# Ideamart_NB-IoT_Dev_Board.net
KiCad netlist of a schematic drawn in EAGLE
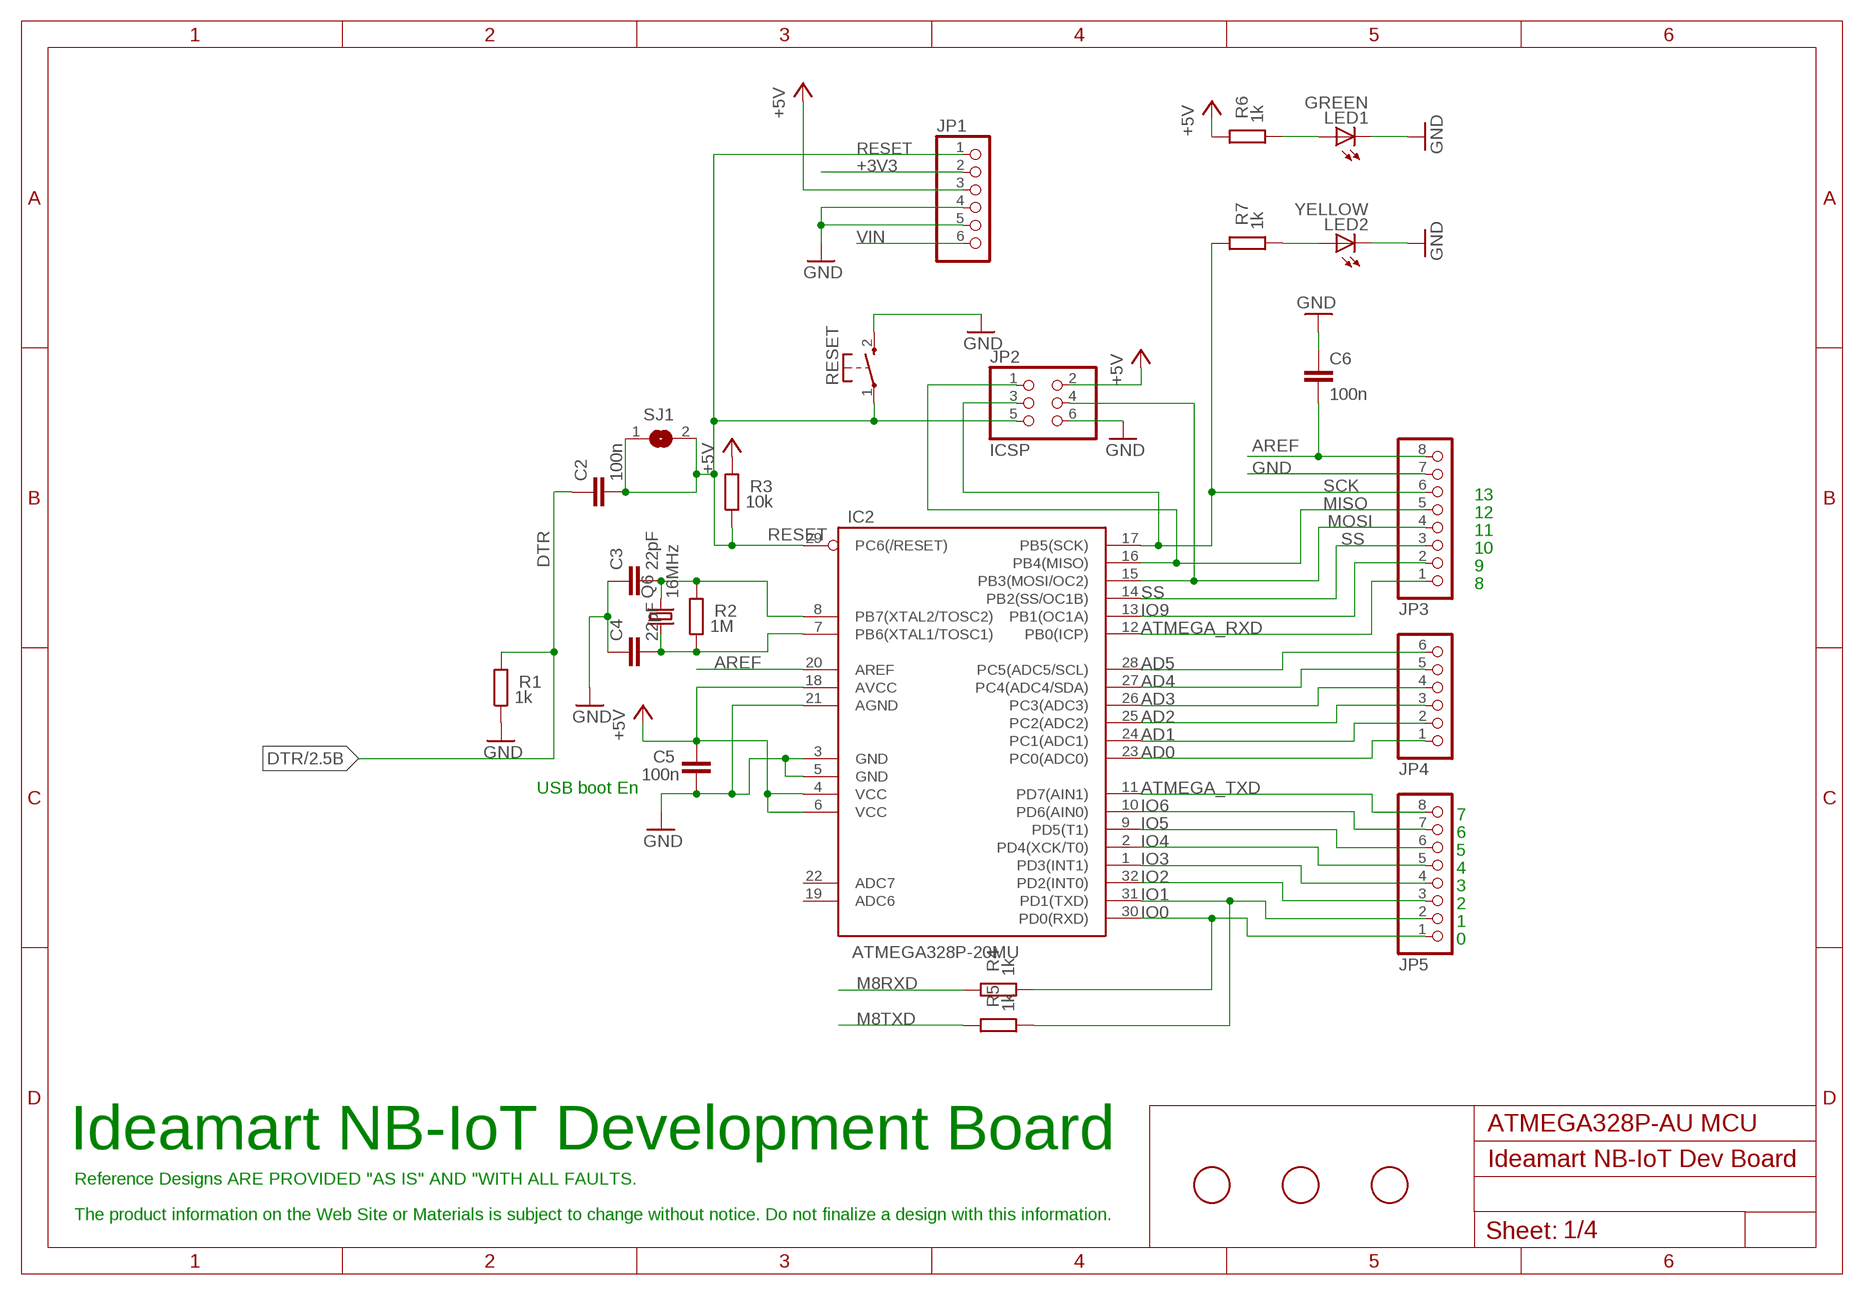
[diagram p0: schematic, sheet 1]
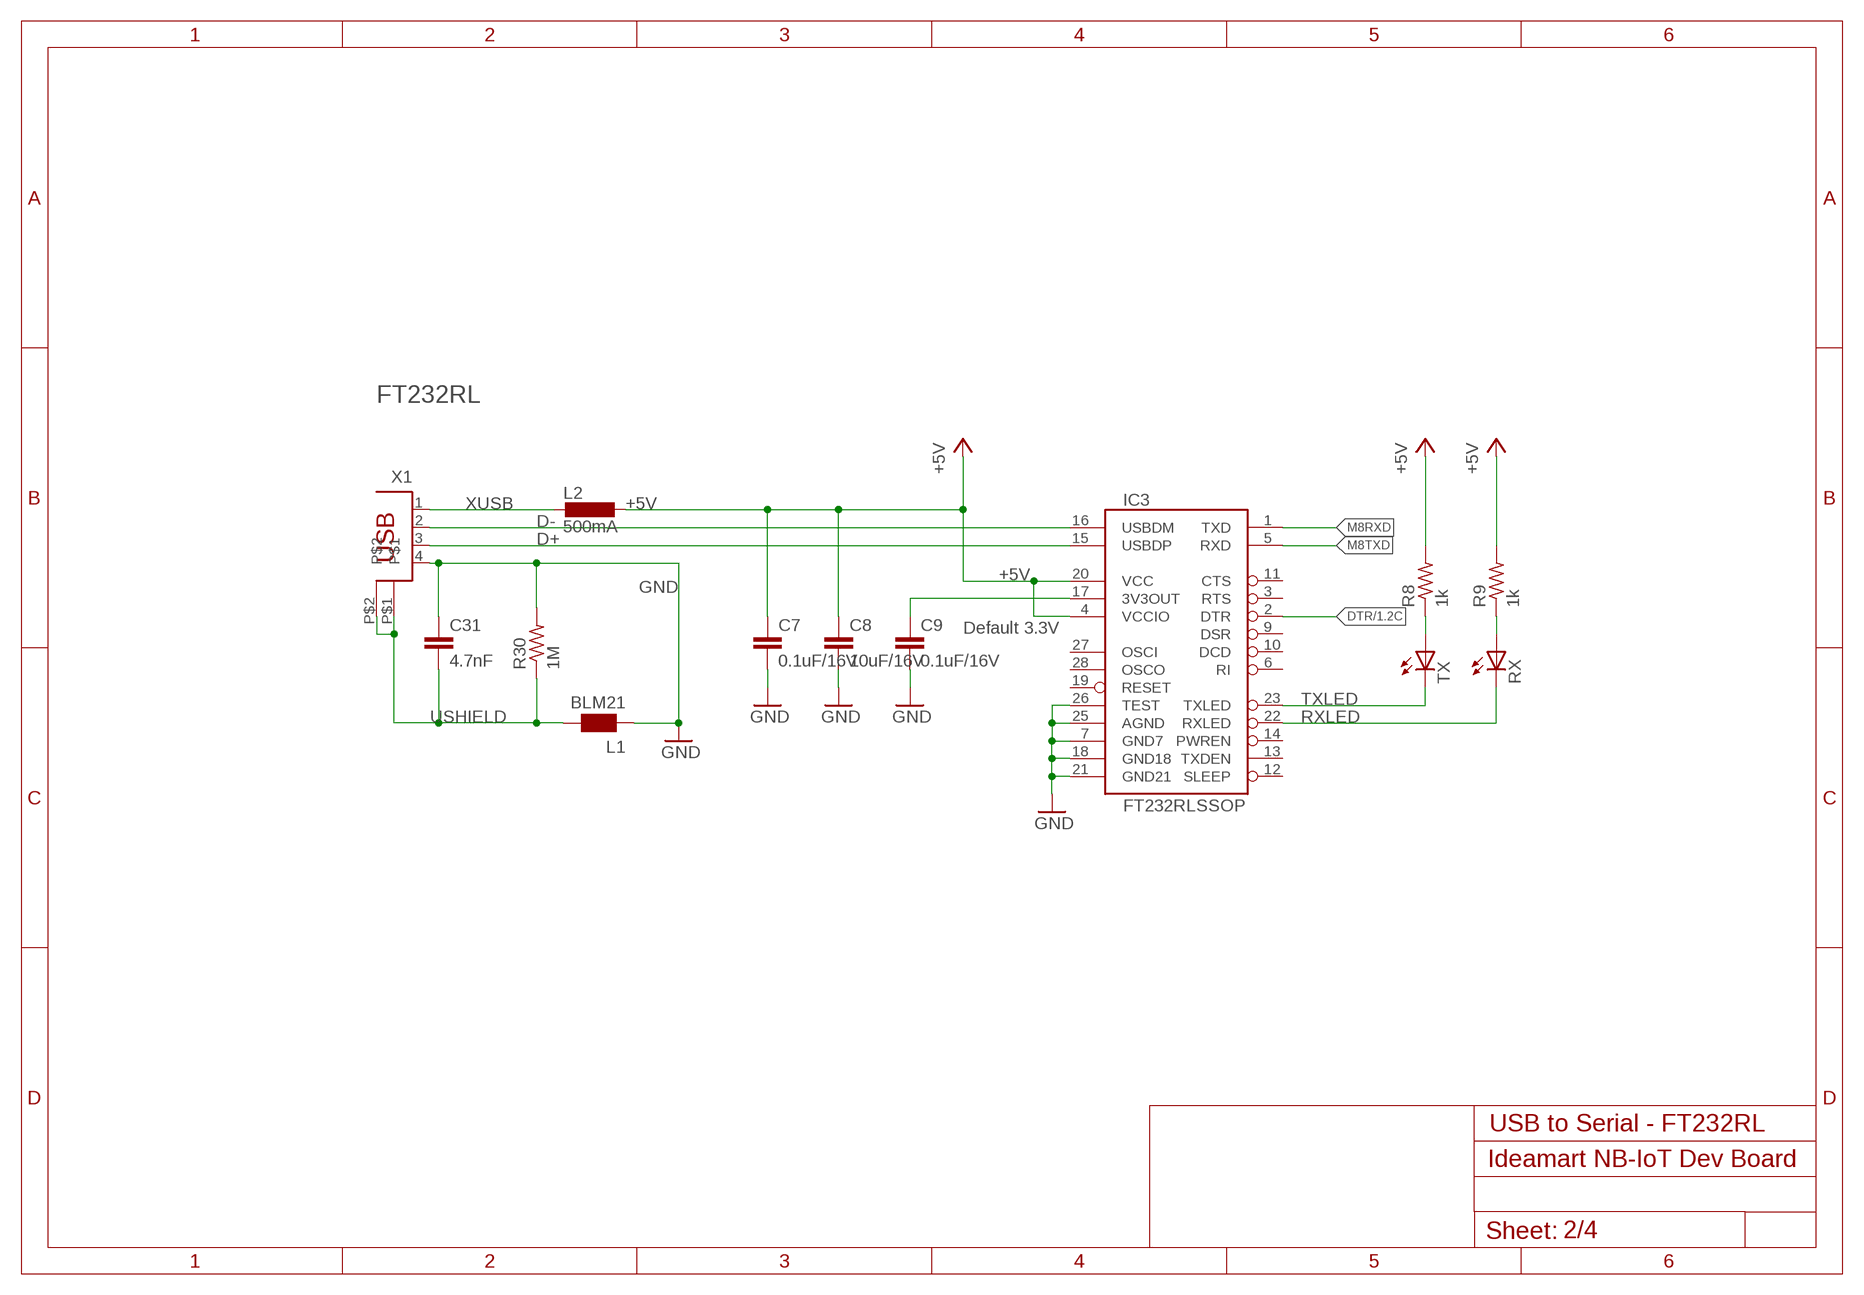
[diagram p1: schematic, sheet 2]
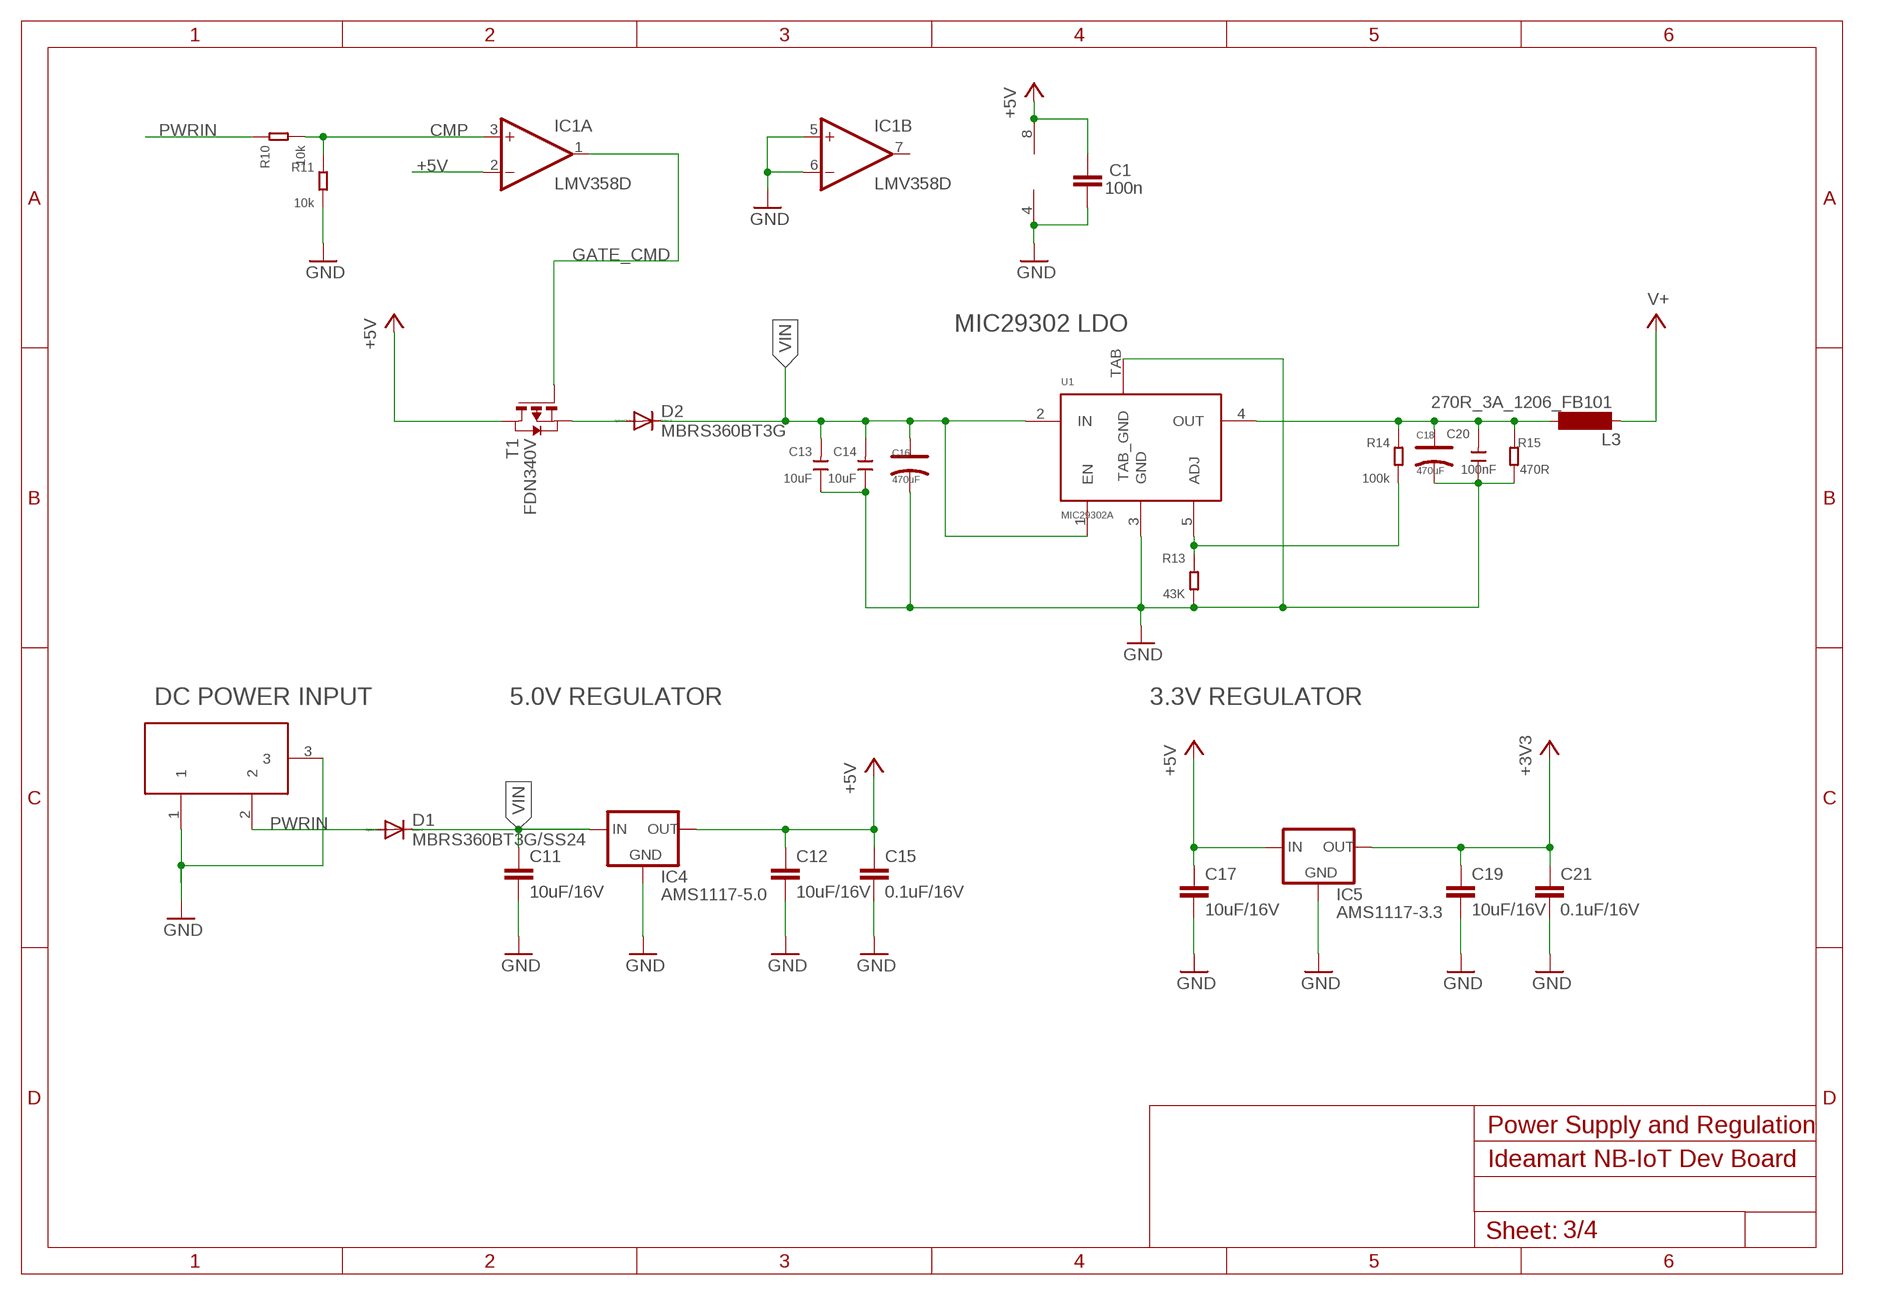
[diagram p2: schematic, sheet 3]
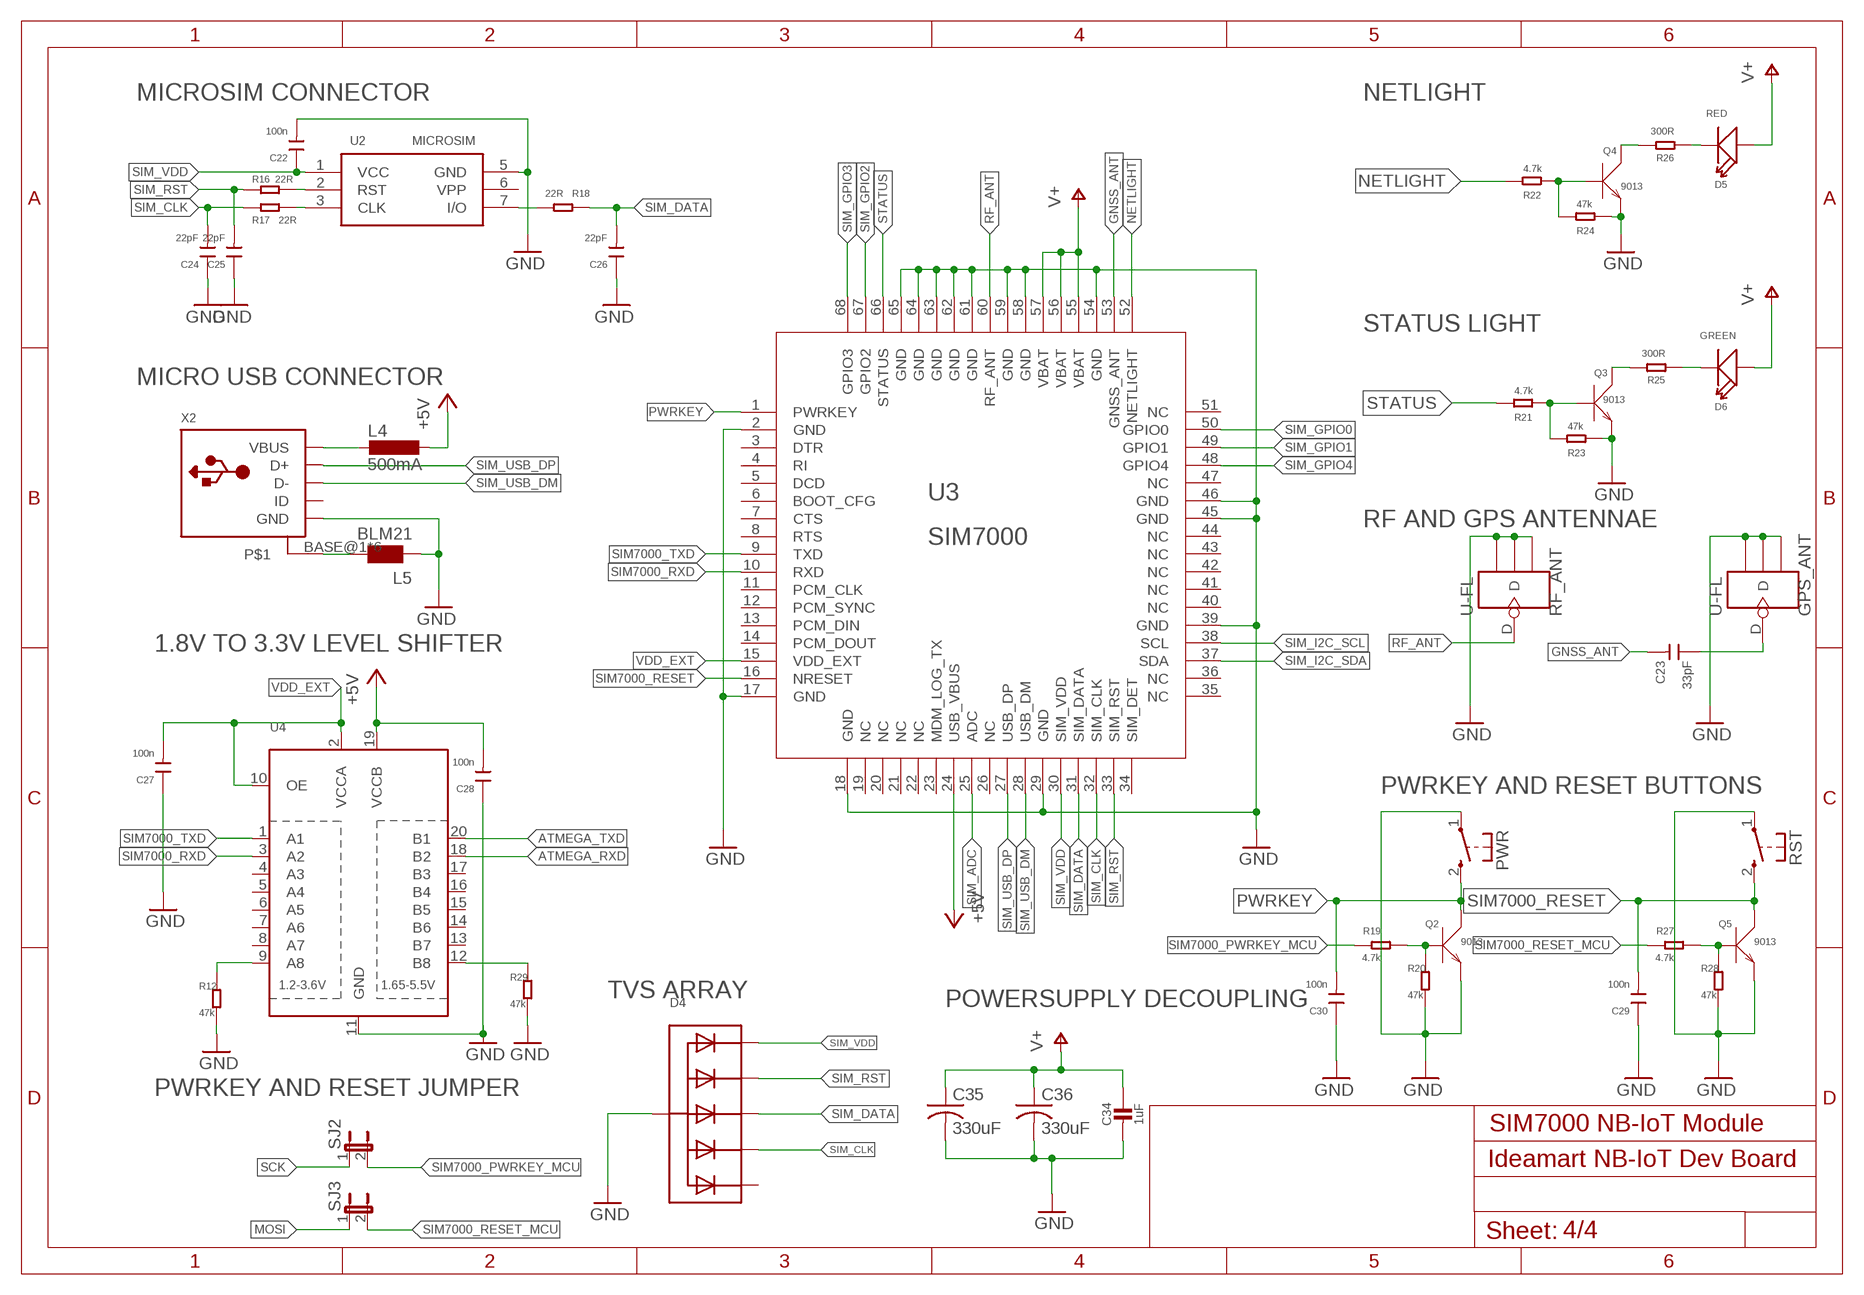
[diagram p3: schematic, sheet 4]

(export (version "E")
  (design (tool "Eeschema 10.0.6"))
  (components
    (comp (ref "C1")
      (value "100n")
      (footprint "eagle-import:C0805")
      (libsource (lib "eagle-import") (part "C-EUC0805"))
    )
    (comp (ref "C10")
      (value "DC21MMX")
      (footprint "eagle-import:DC-21MM")
      (libsource (lib "eagle-import") (part "DC21MMX"))
    )
    (comp (ref "C11")
      (value "10uF/16V")
      (footprint "eagle-import:C0805K")
      (libsource (lib "eagle-import") (part "rcl_C-EUC0805K"))
    )
    (comp (ref "C12")
      (value "10uF/16V")
      (footprint "eagle-import:C0805K")
      (libsource (lib "eagle-import") (part "rcl_C-EUC0805K"))
    )
    (comp (ref "C13")
      (value "10uF")
      (footprint "eagle-import:0805")
      (libsource (lib "eagle-import") (part "C-0805"))
    )
    (comp (ref "C14")
      (value "10uF")
      (footprint "eagle-import:0805")
      (libsource (lib "eagle-import") (part "C-0805"))
    )
    (comp (ref "C15")
      (value "0.1uF/16V")
      (footprint "eagle-import:C0805K")
      (libsource (lib "eagle-import") (part "rcl_C-EUC0805K"))
    )
    (comp (ref "C16")
      (value "470uF")
      (footprint "eagle-import:AVX_D")
      (libsource (lib "eagle-import") (part "006-CAP_AVX_D"))
    )
    (comp (ref "C17")
      (value "10uF/16V")
      (footprint "eagle-import:C0805K")
      (libsource (lib "eagle-import") (part "rcl_C-EUC0805K"))
    )
    (comp (ref "C18")
      (value "470uF")
      (footprint "eagle-import:AVX_D")
      (libsource (lib "eagle-import") (part "006-CAP_AVX_D"))
    )
    (comp (ref "C19")
      (value "10uF/16V")
      (footprint "eagle-import:C0805K")
      (libsource (lib "eagle-import") (part "rcl_C-EUC0805K"))
    )
    (comp (ref "C20")
      (value "100nF")
      (footprint "eagle-import:0805")
      (libsource (lib "eagle-import") (part "C-0805"))
    )
    (comp (ref "C21")
      (value "0.1uF/16V")
      (footprint "eagle-import:C0805K")
      (libsource (lib "eagle-import") (part "rcl_C-EUC0805K"))
    )
    (comp (ref "D1")
      (value "MBRS360BT3G/SS24")
      (footprint "eagle-import:SMB")
      (libsource (lib "eagle-import") (part "DIODE-SMB"))
    )
    (comp (ref "D2")
      (value "MBRS360BT3G")
      (footprint "eagle-import:SMB")
      (libsource (lib "eagle-import") (part "DIODE-SMB"))
    )
    (comp (ref "IC1")
      (value "LMV358D")
      (footprint "eagle-import:SO08")
      (libsource (lib "eagle-import") (part "LM358D"))
    )
    (comp (ref "IC4")
      (value "AMS1117-5.0")
      (footprint "eagle-import:SOT223")
      (libsource (lib "eagle-import") (part "LM1117"))
    )
    (comp (ref "IC5")
      (value "AMS1117-3.3")
      (footprint "eagle-import:SOT223")
      (libsource (lib "eagle-import") (part "LM1117"))
    )
    (comp (ref "L3")
      (value "270R_3A_1206_FB101")
      (footprint "eagle-import:SM-1206")
      (libsource (lib "eagle-import") (part "SM-1206"))
    )
    (comp (ref "R10")
      (value "10k")
      (footprint "eagle-import:0805")
      (libsource (lib "eagle-import") (part "R-0805"))
    )
    (comp (ref "R11")
      (value "10k")
      (footprint "eagle-import:0805")
      (libsource (lib "eagle-import") (part "R-0805"))
    )
    (comp (ref "R13")
      (value "43K")
      (footprint "eagle-import:0805")
      (libsource (lib "eagle-import") (part "R-0805"))
    )
    (comp (ref "R14")
      (value "100k")
      (footprint "eagle-import:0805")
      (libsource (lib "eagle-import") (part "R-0805"))
    )
    (comp (ref "R15")
      (value "470R")
      (footprint "eagle-import:0805")
      (libsource (lib "eagle-import") (part "R-0805"))
    )
    (comp (ref "T1")
      (value "FDN340V")
      (footprint "eagle-import:SOT-23")
      (libsource (lib "eagle-import") (part "PMOSSOT23"))
    )
    (comp (ref "U1")
      (value "MIC29302A")
      (footprint "eagle-import:TO-263A")
      (libsource (lib "eagle-import") (part "MIC29302A"))
    )
    (comp (ref "C2")
      (value "100n")
      (footprint "eagle-import:C0805")
      (libsource (lib "eagle-import") (part "C-EUC0805"))
    )
    (comp (ref "C3")
      (value "22pF")
      (footprint "eagle-import:C0805")
      (libsource (lib "eagle-import") (part "C-EUC0805"))
    )
    (comp (ref "C4")
      (value "22pF")
      (footprint "eagle-import:C0805")
      (libsource (lib "eagle-import") (part "C-EUC0805"))
    )
    (comp (ref "C5")
      (value "100n")
      (footprint "eagle-import:C0805")
      (libsource (lib "eagle-import") (part "C-EUC0805"))
    )
    (comp (ref "C6")
      (value "100n")
      (footprint "eagle-import:C0805")
      (libsource (lib "eagle-import") (part "C-EUC0805"))
    )
    (comp (ref "IC2")
      (value "ATMEGA328P-20MU")
      (footprint "eagle-import:TQFP32-08")
      (libsource (lib "eagle-import") (part "MEGA8-AI"))
    )
    (comp (ref "JP1")
      (value "PINHD-1X6")
      (footprint "eagle-import:1X06")
      (libsource (lib "eagle-import") (part "PINHD-1X6"))
    )
    (comp (ref "JP2")
      (value "ICSP")
      (footprint "eagle-import:2X03")
      (libsource (lib "eagle-import") (part "PINHD-2X3"))
    )
    (comp (ref "JP3")
      (value "PINHD-1X8")
      (footprint "eagle-import:1X08")
      (libsource (lib "eagle-import") (part "PINHD-1X8"))
    )
    (comp (ref "JP4")
      (value "PINHD-1X6")
      (footprint "eagle-import:1X06")
      (libsource (lib "eagle-import") (part "PINHD-1X6"))
    )
    (comp (ref "JP5")
      (value "PINHD-1X8")
      (footprint "eagle-import:1X08")
      (libsource (lib "eagle-import") (part "PINHD-1X8"))
    )
    (comp (ref "LED1")
      (value "GREEN")
      (footprint "eagle-import:CHIP-LED0805")
      (libsource (lib "eagle-import") (part "LEDCHIP-LED0805"))
    )
    (comp (ref "LED2")
      (value "YELLOW")
      (footprint "eagle-import:CHIP-LED0805")
      (libsource (lib "eagle-import") (part "LEDCHIP-LED0805"))
    )
    (comp (ref "M1")
      (value "FIDUCIALMOUNT")
      (footprint "eagle-import:FIDUCIA-MOUNT")
      (libsource (lib "eagle-import") (part "FIDUCIALMOUNT"))
    )
    (comp (ref "M2")
      (value "FIDUCIALMOUNT")
      (footprint "eagle-import:FIDUCIA-MOUNT")
      (libsource (lib "eagle-import") (part "FIDUCIALMOUNT"))
    )
    (comp (ref "M3")
      (value "FIDUCIALMOUNT")
      (footprint "eagle-import:FIDUCIA-MOUNT")
      (libsource (lib "eagle-import") (part "FIDUCIALMOUNT"))
    )
    (comp (ref "Q6")
      (value "16MHz")
      (footprint "eagle-import:CTS406")
      (libsource (lib "eagle-import") (part "CRYSTALCTS406"))
    )
    (comp (ref "R1")
      (value "1k")
      (footprint "eagle-import:R0805")
      (libsource (lib "eagle-import") (part "R-EU_R0805"))
    )
    (comp (ref "R2")
      (value "1M")
      (footprint "eagle-import:R0805")
      (libsource (lib "eagle-import") (part "R-EU_R0805"))
    )
    (comp (ref "R3")
      (value "10k")
      (footprint "eagle-import:R0805")
      (libsource (lib "eagle-import") (part "R-EU_R0805"))
    )
    (comp (ref "R4")
      (value "1k")
      (footprint "eagle-import:R0805")
      (libsource (lib "eagle-import") (part "R-EU_R0805"))
    )
    (comp (ref "R5")
      (value "1k")
      (footprint "eagle-import:R0805")
      (libsource (lib "eagle-import") (part "R-EU_R0805"))
    )
    (comp (ref "R6")
      (value "1k")
      (footprint "eagle-import:R0805")
      (libsource (lib "eagle-import") (part "R-EU_R0805"))
    )
    (comp (ref "R7")
      (value "1k")
      (footprint "eagle-import:R0805")
      (libsource (lib "eagle-import") (part "R-EU_R0805"))
    )
    (comp (ref "RESET")
      (value "KSS-2EG4430")
      (footprint "eagle-import:KSS-2EG4430")
      (libsource (lib "eagle-import") (part "KSS-2EG4430"))
    )
    (comp (ref "SJ1") (value "SJ") (footprint "eagle-import:SJ") (libsource (lib "eagle-import") (part "SJ")))
    (comp (ref "C7")
      (value "0.1uF/16V")
      (footprint "eagle-import:C0805K")
      (libsource (lib "eagle-import") (part "rcl_C-EUC0805K"))
    )
    (comp (ref "C8")
      (value "10uF/16V")
      (footprint "eagle-import:C0805K")
      (libsource (lib "eagle-import") (part "rcl_C-EUC0805K"))
    )
    (comp (ref "C9")
      (value "0.1uF/16V")
      (footprint "eagle-import:C0805K")
      (libsource (lib "eagle-import") (part "rcl_C-EUC0805K"))
    )
    (comp (ref "C31")
      (value "4.7nF")
      (footprint "eagle-import:C0805K")
      (libsource (lib "eagle-import") (part "rcl_C-EUC0805K"))
    )
    (comp (ref "IC3")
      (value "FT232RLSSOP")
      (footprint "eagle-import:SSOP28DB")
      (libsource (lib "eagle-import") (part "FT232RLSSOP"))
    )
    (comp (ref "L1")
      (value "BLM21")
      (footprint "eagle-import:0805")
      (libsource (lib "eagle-import") (part "WE-CBF_0805"))
    )
    (comp (ref "L2")
      (value "500mA")
      (footprint "eagle-import:L1812")
      (libsource (lib "eagle-import") (part "L-EUL1812"))
    )
    (comp (ref "R8")
      (value "1k")
      (footprint "eagle-import:M0805")
      (libsource (lib "eagle-import") (part "R-US_M0805"))
    )
    (comp (ref "R9")
      (value "1k")
      (footprint "eagle-import:M0805")
      (libsource (lib "eagle-import") (part "R-US_M0805"))
    )
    (comp (ref "R30")
      (value "1M")
      (footprint "eagle-import:M0805")
      (libsource (lib "eagle-import") (part "R-US_M0805"))
    )
    (comp (ref "RX")
      (value "LEDCHIP-LED0805")
      (footprint "eagle-import:CHIP-LED0805")
      (libsource (lib "eagle-import") (part "LEDCHIP-LED0805"))
    )
    (comp (ref "TX")
      (value "LEDCHIP-LED0805")
      (footprint "eagle-import:CHIP-LED0805")
      (libsource (lib "eagle-import") (part "LEDCHIP-LED0805"))
    )
    (comp (ref "X1")
      (value "PN61729")
      (footprint "eagle-import:PN61729")
      (libsource (lib "eagle-import") (part "PN61729"))
    )
    (comp (ref "C22")
      (value "100n")
      (footprint "eagle-import:0805")
      (libsource (lib "eagle-import") (part "C-0805"))
    )
    (comp (ref "C23")
      (value "33pF")
      (footprint "eagle-import:0805")
      (libsource (lib "eagle-import") (part "C-0805"))
    )
    (comp (ref "C24")
      (value "22pF")
      (footprint "eagle-import:0805")
      (libsource (lib "eagle-import") (part "C-0805"))
    )
    (comp (ref "C25")
      (value "22pF")
      (footprint "eagle-import:0805")
      (libsource (lib "eagle-import") (part "C-0805"))
    )
    (comp (ref "C26")
      (value "22pF")
      (footprint "eagle-import:0805")
      (libsource (lib "eagle-import") (part "C-0805"))
    )
    (comp (ref "C27")
      (value "100n")
      (footprint "eagle-import:0805")
      (libsource (lib "eagle-import") (part "C-0805"))
    )
    (comp (ref "C28")
      (value "100n")
      (footprint "eagle-import:0805")
      (libsource (lib "eagle-import") (part "C-0805"))
    )
    (comp (ref "C29")
      (value "100n")
      (footprint "eagle-import:0805")
      (libsource (lib "eagle-import") (part "C-0805"))
    )
    (comp (ref "C30")
      (value "100n")
      (footprint "eagle-import:0805")
      (libsource (lib "eagle-import") (part "C-0805"))
    )
    (comp (ref "C34")
      (value "1uF")
      (footprint "eagle-import:_0805")
      (libsource (lib "eagle-import") (part "CAP_CERAMIC_0805"))
    )
    (comp (ref "C35")
      (value "330uF")
      (footprint "eagle-import:C1210")
      (libsource (lib "eagle-import") (part "C-USC1210"))
    )
    (comp (ref "C36")
      (value "330uF")
      (footprint "eagle-import:C1210")
      (libsource (lib "eagle-import") (part "C-USC1210"))
    )
    (comp (ref "D4")
      (value "TVSARRAY_5LANE")
      (footprint "eagle-import:SOT363")
      (libsource (lib "eagle-import") (part "TVSARRAY_5LANE"))
    )
    (comp (ref "D5")
      (value "RED")
      (footprint "eagle-import:LED-0805")
      (libsource (lib "eagle-import") (part "LED'0805'"))
    )
    (comp (ref "D6")
      (value "GREEN")
      (footprint "eagle-import:LED-0805")
      (libsource (lib "eagle-import") (part "LED'0805'"))
    )
    (comp (ref "GPS_ANT")
      (value "U-FL")
      (footprint "eagle-import:4P-U-FL")
      (libsource (lib "eagle-import") (part "ANTENNA-U-FL"))
    )
    (comp (ref "L4")
      (value "500mA")
      (footprint "eagle-import:L1812")
      (libsource (lib "eagle-import") (part "L-EUL1812"))
    )
    (comp (ref "L5")
      (value "BLM21")
      (footprint "eagle-import:0805")
      (libsource (lib "eagle-import") (part "WE-CBF_0805"))
    )
    (comp (ref "PWR")
      (value "KSS-2EG4430")
      (footprint "eagle-import:KSS-2EG4430")
      (libsource (lib "eagle-import") (part "KSS-2EG4430"))
    )
    (comp (ref "Q2")
      (value "9013")
      (footprint "eagle-import:SOT23")
      (libsource (lib "eagle-import") (part "TRANSISTOR-NPN-SOT23"))
    )
    (comp (ref "Q3")
      (value "9013")
      (footprint "eagle-import:SOT23")
      (libsource (lib "eagle-import") (part "TRANSISTOR-NPN-SOT23"))
    )
    (comp (ref "Q4")
      (value "9013")
      (footprint "eagle-import:SOT23")
      (libsource (lib "eagle-import") (part "TRANSISTOR-NPN-SOT23"))
    )
    (comp (ref "Q5")
      (value "9013")
      (footprint "eagle-import:SOT23")
      (libsource (lib "eagle-import") (part "TRANSISTOR-NPN-SOT23"))
    )
    (comp (ref "R12")
      (value "47k")
      (footprint "eagle-import:0805")
      (libsource (lib "eagle-import") (part "R-0805"))
    )
    (comp (ref "R16")
      (value "22R")
      (footprint "eagle-import:0805")
      (libsource (lib "eagle-import") (part "R-0805"))
    )
    (comp (ref "R17")
      (value "22R")
      (footprint "eagle-import:0805")
      (libsource (lib "eagle-import") (part "R-0805"))
    )
    (comp (ref "R18")
      (value "22R")
      (footprint "eagle-import:0805")
      (libsource (lib "eagle-import") (part "R-0805"))
    )
    (comp (ref "R19")
      (value "4.7k")
      (footprint "eagle-import:0805")
      (libsource (lib "eagle-import") (part "R-0805"))
    )
    (comp (ref "R20")
      (value "47k")
      (footprint "eagle-import:0805")
      (libsource (lib "eagle-import") (part "R-0805"))
    )
    (comp (ref "R21")
      (value "4.7k")
      (footprint "eagle-import:0805")
      (libsource (lib "eagle-import") (part "R-0805"))
    )
    (comp (ref "R22")
      (value "4.7k")
      (footprint "eagle-import:0805")
      (libsource (lib "eagle-import") (part "R-0805"))
    )
    (comp (ref "R23")
      (value "47k")
      (footprint "eagle-import:0805")
      (libsource (lib "eagle-import") (part "R-0805"))
    )
    (comp (ref "R24")
      (value "47k")
      (footprint "eagle-import:0805")
      (libsource (lib "eagle-import") (part "R-0805"))
    )
    (comp (ref "R25")
      (value "300R")
      (footprint "eagle-import:0805")
      (libsource (lib "eagle-import") (part "R-0805"))
    )
    (comp (ref "R26")
      (value "300R")
      (footprint "eagle-import:0805")
      (libsource (lib "eagle-import") (part "R-0805"))
    )
    (comp (ref "R27")
      (value "4.7k")
      (footprint "eagle-import:0805")
      (libsource (lib "eagle-import") (part "R-0805"))
    )
    (comp (ref "R28")
      (value "47k")
      (footprint "eagle-import:0805")
      (libsource (lib "eagle-import") (part "R-0805"))
    )
    (comp (ref "R29")
      (value "47k")
      (footprint "eagle-import:0805")
      (libsource (lib "eagle-import") (part "R-0805"))
    )
    (comp (ref "RF_ANT")
      (value "U-FL")
      (footprint "eagle-import:4P-U-FL")
      (libsource (lib "eagle-import") (part "ANTENNA-U-FL"))
    )
    (comp (ref "RST")
      (value "KSS-2EG4430")
      (footprint "eagle-import:KSS-2EG4430")
      (libsource (lib "eagle-import") (part "KSS-2EG4430"))
    )
    (comp (ref "SJ2")
      (value "SPARKFUN-PASSIVES_JUMPER-PTH-2-NC")
      (footprint "eagle-import:SPARKFUN-PASSIVES_PTH-JUMPER-NC_BOTTOM_NO_SILK")
      (libsource (lib "eagle-import") (part "SPARKFUN-PASSIVES_JUMPER-PTH-2-NC"))
    )
    (comp (ref "SJ3")
      (value "SPARKFUN-PASSIVES_JUMPER-PTH-2-NC")
      (footprint "eagle-import:SPARKFUN-PASSIVES_PTH-JUMPER-NC_BOTTOM_NO_SILK")
      (libsource (lib "eagle-import") (part "SPARKFUN-PASSIVES_JUMPER-PTH-2-NC"))
    )
    (comp (ref "U2")
      (value "MICROSIM")
      (footprint "eagle-import:MICROSIM")
      (libsource (lib "eagle-import") (part "MICROSIM"))
    )
    (comp (ref "U3")
      (value "SIM7000")
      (footprint "eagle-import:SIM7000")
      (libsource (lib "eagle-import") (part "SIM7000"))
    )
    (comp (ref "U4")
      (value "TXB0108PWR")
      (footprint "eagle-import:TSSOP20")
      (libsource (lib "eagle-import") (part "TXB0108PWR"))
    )
    (comp (ref "X2")
      (value "USB_MICRO_20329_V2")
      (footprint "eagle-import:4UCONN_20329_V2")
      (libsource (lib "eagle-import") (part "USB_MICRO_20329_V2"))
    )
  )
  (nets
    (net (code "1") (name "+3V3") (class "Default")
      (node (ref "C19") (pin "1") (pinfunction "1_1") (pintype "passive"))
      (node (ref "C21") (pin "1") (pinfunction "1_1") (pintype "passive"))
      (node (ref "IC5") (pin "2") (pinfunction "OUT_2") (pintype "passive"))
      (node (ref "JP1") (pin "2") (pinfunction "2_2") (pintype "passive"))
    )
    (net (code "2") (name "+5V") (class "Default")
      (node (ref "C1") (pin "2") (pinfunction "2_2") (pintype "passive"))
      (node (ref "C12") (pin "1") (pinfunction "1_1") (pintype "passive"))
      (node (ref "C15") (pin "1") (pinfunction "1_1") (pintype "passive"))
      (node (ref "C17") (pin "1") (pinfunction "1_1") (pintype "passive"))
      (node (ref "C28") (pin "2") (pinfunction "2_2") (pintype "passive"))
      (node (ref "C5") (pin "2") (pinfunction "2_2") (pintype "passive"))
      (node (ref "C7") (pin "1") (pinfunction "1_1") (pintype "passive"))
      (node (ref "C8") (pin "1") (pinfunction "1_1") (pintype "passive"))
      (node (ref "IC1") (pin "2") (pinfunction "-IN_2") (pintype "input"))
      (node (ref "IC1") (pin "8") (pinfunction "V+_8") (pintype "power_in"))
      (node (ref "IC2") (pin "18") (pinfunction "AVCC_18") (pintype "bidirectional"))
      (node (ref "IC2") (pin "4") (pinfunction "VCC_4") (pintype "bidirectional"))
      (node (ref "IC2") (pin "6") (pinfunction "VCC_6") (pintype "bidirectional"))
      (node (ref "IC3") (pin "20") (pinfunction "VCC_20") (pintype "power_in"))
      (node (ref "IC3") (pin "4") (pinfunction "VCCIO_4") (pintype "power_in"))
      (node (ref "IC4") (pin "2") (pinfunction "OUT_2") (pintype "passive"))
      (node (ref "IC5") (pin "3") (pinfunction "IN_3") (pintype "input"))
      (node (ref "JP1") (pin "3") (pinfunction "3_3") (pintype "passive"))
      (node (ref "JP2") (pin "2") (pinfunction "2_2") (pintype "passive"))
      (node (ref "L2") (pin "1") (pinfunction "1_1") (pintype "passive"))
      (node (ref "L4") (pin "1") (pinfunction "1_1") (pintype "passive"))
      (node (ref "R3") (pin "2") (pinfunction "2_2") (pintype "passive"))
      (node (ref "R6") (pin "2") (pinfunction "2_2") (pintype "passive"))
      (node (ref "R8") (pin "2") (pinfunction "2_2") (pintype "passive"))
      (node (ref "R9") (pin "2") (pinfunction "2_2") (pintype "passive"))
      (node (ref "T1") (pin "1") (pinfunction "D_1") (pintype "passive"))
      (node (ref "U3") (pin "24") (pinfunction "USB_VBUS_24") (pintype "output"))
      (node (ref "U4") (pin "19") (pinfunction "VCCB_19") (pintype "bidirectional"))
    )
    (net (code "3") (name "AD0") (class "Default")
      (node (ref "IC2") (pin "23") (pinfunction "PC0(ADC0)_23") (pintype "bidirectional"))
      (node (ref "JP4") (pin "1") (pinfunction "1_1") (pintype "passive"))
    )
    (net (code "4") (name "AD1") (class "Default")
      (node (ref "IC2") (pin "24") (pinfunction "PC1(ADC1)_24") (pintype "bidirectional"))
      (node (ref "JP4") (pin "2") (pinfunction "2_2") (pintype "passive"))
    )
    (net (code "5") (name "AD2") (class "Default")
      (node (ref "IC2") (pin "25") (pinfunction "PC2(ADC2)_25") (pintype "bidirectional"))
      (node (ref "JP4") (pin "3") (pinfunction "3_3") (pintype "passive"))
    )
    (net (code "6") (name "AD3") (class "Default")
      (node (ref "IC2") (pin "26") (pinfunction "PC3(ADC3)_26") (pintype "bidirectional"))
      (node (ref "JP4") (pin "4") (pinfunction "4_4") (pintype "passive"))
    )
    (net (code "7") (name "AD4") (class "Default")
      (node (ref "IC2") (pin "27") (pinfunction "PC4(ADC4/SDA)_27") (pintype "bidirectional"))
      (node (ref "JP4") (pin "5") (pinfunction "5_5") (pintype "passive"))
    )
    (net (code "8") (name "AD5") (class "Default")
      (node (ref "IC2") (pin "28") (pinfunction "PC5(ADC5/SCL)_28") (pintype "bidirectional"))
      (node (ref "JP4") (pin "6") (pinfunction "6_6") (pintype "passive"))
    )
    (net (code "9") (name "AREF") (class "Default")
      (node (ref "C6") (pin "2") (pinfunction "2_2") (pintype "passive"))
      (node (ref "IC2") (pin "20") (pinfunction "AREF_20") (pintype "bidirectional"))
      (node (ref "JP3") (pin "8") (pinfunction "8_8") (pintype "passive"))
    )
    (net (code "10") (name "ATMEGA_RXD") (class "Default")
      (node (ref "IC2") (pin "12") (pinfunction "PB0(ICP)_12") (pintype "bidirectional"))
      (node (ref "JP3") (pin "1") (pinfunction "1_1") (pintype "passive"))
      (node (ref "U4") (pin "18") (pinfunction "B2_18") (pintype "bidirectional"))
    )
    (net (code "11") (name "ATMEGA_TXD") (class "Default")
      (node (ref "IC2") (pin "11") (pinfunction "PD7(AIN1)_11") (pintype "bidirectional"))
      (node (ref "JP5") (pin "8") (pinfunction "8_8") (pintype "passive"))
      (node (ref "U4") (pin "20") (pinfunction "B1_20") (pintype "bidirectional"))
    )
    (net (code "12") (name "CMP") (class "Default")
      (node (ref "IC1") (pin "3") (pinfunction "+IN_3") (pintype "input"))
      (node (ref "R10") (pin "1") (pinfunction "1_1") (pintype "passive"))
      (node (ref "R11") (pin "2") (pinfunction "2_2") (pintype "passive"))
    )
    (net (code "13") (name "D+") (class "Default")
      (node (ref "IC3") (pin "15") (pinfunction "USBDP_15") (pintype "bidirectional"))
      (node (ref "X1") (pin "3") (pinfunction "3_3") (pintype "bidirectional"))
    )
    (net (code "14") (name "D-") (class "Default")
      (node (ref "IC3") (pin "16") (pinfunction "USBDM_16") (pintype "bidirectional"))
      (node (ref "X1") (pin "2") (pinfunction "2_2") (pintype "bidirectional"))
    )
    (net (code "15") (name "DTR") (class "Default")
      (node (ref "C2") (pin "1") (pinfunction "1_1") (pintype "passive"))
      (node (ref "IC3") (pin "2") (pinfunction "DTR_2") (pintype "output"))
      (node (ref "R1") (pin "2") (pinfunction "2_2") (pintype "passive"))
    )
    (net (code "16") (name "GATE_CMD") (class "Default")
      (node (ref "IC1") (pin "1") (pinfunction "OUT_1") (pintype "output"))
      (node (ref "T1") (pin "3") (pinfunction "G_3") (pintype "passive"))
    )
    (net (code "17") (name "GND") (class "Default")
      (node (ref "C1") (pin "1") (pinfunction "1_1") (pintype "passive"))
      (node (ref "C10") (pin "1") (pinfunction "1_1") (pintype "power_in"))
      (node (ref "C10") (pin "3") (pinfunction "3_3") (pintype "power_in"))
      (node (ref "C11") (pin "2") (pinfunction "2_2") (pintype "passive"))
      (node (ref "C12") (pin "2") (pinfunction "2_2") (pintype "passive"))
      (node (ref "C13") (pin "1") (pinfunction "1_1") (pintype "passive"))
      (node (ref "C14") (pin "1") (pinfunction "1_1") (pintype "passive"))
      (node (ref "C15") (pin "2") (pinfunction "2_2") (pintype "passive"))
      (node (ref "C16") (pin "-") (pinfunction "-_-") (pintype "passive"))
      (node (ref "C17") (pin "2") (pinfunction "2_2") (pintype "passive"))
      (node (ref "C18") (pin "-") (pinfunction "-_-") (pintype "passive"))
      (node (ref "C19") (pin "2") (pinfunction "2_2") (pintype "passive"))
      (node (ref "C20") (pin "1") (pinfunction "1_1") (pintype "passive"))
      (node (ref "C21") (pin "2") (pinfunction "2_2") (pintype "passive"))
      (node (ref "C22") (pin "2") (pinfunction "2_2") (pintype "passive"))
      (node (ref "C24") (pin "1") (pinfunction "1_1") (pintype "passive"))
      (node (ref "C25") (pin "1") (pinfunction "1_1") (pintype "passive"))
      (node (ref "C26") (pin "1") (pinfunction "1_1") (pintype "passive"))
      (node (ref "C27") (pin "1") (pinfunction "1_1") (pintype "passive"))
      (node (ref "C28") (pin "1") (pinfunction "1_1") (pintype "passive"))
      (node (ref "C29") (pin "1") (pinfunction "1_1") (pintype "passive"))
      (node (ref "C3") (pin "1") (pinfunction "1_1") (pintype "passive"))
      (node (ref "C30") (pin "1") (pinfunction "1_1") (pintype "passive"))
      (node (ref "C31") (pin "1") (pinfunction "1_1") (pintype "passive"))
      (node (ref "C34") (pin "2") (pinfunction "2_2") (pintype "passive"))
      (node (ref "C35") (pin "2") (pinfunction "2_2") (pintype "passive"))
      (node (ref "C36") (pin "2") (pinfunction "2_2") (pintype "passive"))
      (node (ref "C4") (pin "1") (pinfunction "1_1") (pintype "passive"))
      (node (ref "C5") (pin "1") (pinfunction "1_1") (pintype "passive"))
      (node (ref "C6") (pin "1") (pinfunction "1_1") (pintype "passive"))
      (node (ref "C7") (pin "2") (pinfunction "2_2") (pintype "passive"))
      (node (ref "C8") (pin "2") (pinfunction "2_2") (pintype "passive"))
      (node (ref "C9") (pin "2") (pinfunction "2_2") (pintype "passive"))
      (node (ref "D4") (pin "2") (pinfunction "A_2") (pintype "passive"))
      (node (ref "GPS_ANT") (pin "GND1") (pinfunction "GND1_GND1") (pintype "bidirectional"))
      (node (ref "GPS_ANT") (pin "GND2") (pinfunction "GND2_GND2") (pintype "bidirectional"))
      (node (ref "GPS_ANT") (pin "GND3") (pinfunction "GND3_GND3") (pintype "bidirectional"))
      (node (ref "IC1") (pin "4") (pinfunction "V-_4") (pintype "power_in"))
      (node (ref "IC1") (pin "5") (pinfunction "+IN_5") (pintype "input"))
      (node (ref "IC1") (pin "6") (pinfunction "-IN_6") (pintype "input"))
      (node (ref "IC2") (pin "21") (pinfunction "AGND_21") (pintype "bidirectional"))
      (node (ref "IC2") (pin "3") (pinfunction "GND_3") (pintype "bidirectional"))
      (node (ref "IC2") (pin "5") (pinfunction "GND_5") (pintype "bidirectional"))
      (node (ref "IC3") (pin "18") (pinfunction "GND18_18") (pintype "power_in"))
      (node (ref "IC3") (pin "21") (pinfunction "GND21_21") (pintype "power_in"))
      (node (ref "IC3") (pin "25") (pinfunction "AGND_25") (pintype "power_in"))
      (node (ref "IC3") (pin "26") (pinfunction "TEST_26") (pintype "input"))
      (node (ref "IC3") (pin "7") (pinfunction "GND7_7") (pintype "power_in"))
      (node (ref "IC4") (pin "1") (pinfunction "GND_1") (pintype "input"))
      (node (ref "IC5") (pin "1") (pinfunction "GND_1") (pintype "input"))
      (node (ref "JP1") (pin "4") (pinfunction "4_4") (pintype "passive"))
      (node (ref "JP1") (pin "5") (pinfunction "5_5") (pintype "passive"))
      (node (ref "JP2") (pin "6") (pinfunction "6_6") (pintype "passive"))
      (node (ref "JP3") (pin "7") (pinfunction "7_7") (pintype "passive"))
      (node (ref "L1") (pin "1") (pinfunction "1_1") (pintype "passive"))
      (node (ref "L5") (pin "1") (pinfunction "1_1") (pintype "passive"))
      (node (ref "LED1") (pin "C") (pinfunction "C_C") (pintype "passive"))
      (node (ref "LED2") (pin "C") (pinfunction "C_C") (pintype "passive"))
      (node (ref "PWR") (pin "1") (pinfunction "P_1") (pintype "passive"))
      (node (ref "Q2") (pin "2") (pinfunction "E_2") (pintype "passive"))
      (node (ref "Q3") (pin "2") (pinfunction "E_2") (pintype "passive"))
      (node (ref "Q4") (pin "2") (pinfunction "E_2") (pintype "passive"))
      (node (ref "Q5") (pin "2") (pinfunction "E_2") (pintype "passive"))
      (node (ref "R1") (pin "1") (pinfunction "1_1") (pintype "passive"))
      (node (ref "R11") (pin "1") (pinfunction "1_1") (pintype "passive"))
      (node (ref "R12") (pin "2") (pinfunction "2_2") (pintype "passive"))
      (node (ref "R13") (pin "1") (pinfunction "1_1") (pintype "passive"))
      (node (ref "R15") (pin "1") (pinfunction "1_1") (pintype "passive"))
      (node (ref "R20") (pin "2") (pinfunction "2_2") (pintype "passive"))
      (node (ref "R23") (pin "2") (pinfunction "2_2") (pintype "passive"))
      (node (ref "R24") (pin "2") (pinfunction "2_2") (pintype "passive"))
      (node (ref "R28") (pin "2") (pinfunction "2_2") (pintype "passive"))
      (node (ref "R29") (pin "2") (pinfunction "2_2") (pintype "passive"))
      (node (ref "R30") (pin "2") (pinfunction "2_2") (pintype "passive"))
      (node (ref "RESET") (pin "2") (pinfunction "S_2") (pintype "passive"))
      (node (ref "RF_ANT") (pin "GND1") (pinfunction "GND1_GND1") (pintype "bidirectional"))
      (node (ref "RF_ANT") (pin "GND2") (pinfunction "GND2_GND2") (pintype "bidirectional"))
      (node (ref "RF_ANT") (pin "GND3") (pinfunction "GND3_GND3") (pintype "bidirectional"))
      (node (ref "RST") (pin "1") (pinfunction "P_1") (pintype "passive"))
      (node (ref "U1") (pin "3") (pinfunction "GND_3") (pintype "bidirectional"))
      (node (ref "U1") (pin "TAB") (pinfunction "TAB_GND_TAB") (pintype "bidirectional"))
      (node (ref "U2") (pin "5") (pinfunction "GND_5") (pintype "bidirectional"))
      (node (ref "U3") (pin "17") (pinfunction "GND_17") (pintype "power_in"))
      (node (ref "U3") (pin "18") (pinfunction "GND_18") (pintype "power_in"))
      (node (ref "U3") (pin "2") (pinfunction "GND_2") (pintype "power_in"))
      (node (ref "U3") (pin "29") (pinfunction "GND_29") (pintype "power_in"))
      (node (ref "U3") (pin "39") (pinfunction "GND_39") (pintype "power_in"))
      (node (ref "U3") (pin "45") (pinfunction "GND_45") (pintype "power_in"))
      (node (ref "U3") (pin "46") (pinfunction "GND_46") (pintype "power_in"))
      (node (ref "U3") (pin "54") (pinfunction "GND_54") (pintype "power_in"))
      (node (ref "U3") (pin "58") (pinfunction "GND_58") (pintype "output"))
      (node (ref "U3") (pin "59") (pinfunction "GND_59") (pintype "bidirectional"))
      (node (ref "U3") (pin "61") (pinfunction "GND_61") (pintype "input"))
      (node (ref "U3") (pin "62") (pinfunction "GND_62") (pintype "output"))
      (node (ref "U3") (pin "63") (pinfunction "GND_63") (pintype "output"))
      (node (ref "U3") (pin "64") (pinfunction "GND_64") (pintype "input"))
      (node (ref "U3") (pin "65") (pinfunction "GND_65") (pintype "bidirectional"))
      (node (ref "U4") (pin "11") (pinfunction "GND_11") (pintype "bidirectional"))
      (node (ref "X1") (pin "4") (pinfunction "4_4") (pintype "bidirectional"))
      (node (ref "X2") (pin "GND") (pinfunction "GND_GND") (pintype "power_in"))
    )
    (net (code "18") (name "GNSS_ANT") (class "Default")
      (node (ref "C23") (pin "2") (pinfunction "2_2") (pintype "passive"))
      (node (ref "U3") (pin "53") (pinfunction "GNSS_ANT_53") (pintype "power_in"))
    )
    (net (code "19") (name "IO0") (class "Default")
      (node (ref "IC2") (pin "30") (pinfunction "PD0(RXD)_30") (pintype "bidirectional"))
      (node (ref "JP5") (pin "1") (pinfunction "1_1") (pintype "passive"))
      (node (ref "R4") (pin "1") (pinfunction "1_1") (pintype "passive"))
    )
    (net (code "20") (name "IO1") (class "Default")
      (node (ref "IC2") (pin "31") (pinfunction "PD1(TXD)_31") (pintype "bidirectional"))
      (node (ref "JP5") (pin "2") (pinfunction "2_2") (pintype "passive"))
      (node (ref "R5") (pin "1") (pinfunction "1_1") (pintype "passive"))
    )
    (net (code "21") (name "IO2") (class "Default")
      (node (ref "IC2") (pin "32") (pinfunction "PD2(INT0)_32") (pintype "bidirectional"))
      (node (ref "JP5") (pin "3") (pinfunction "3_3") (pintype "passive"))
    )
    (net (code "22") (name "IO3") (class "Default")
      (node (ref "IC2") (pin "1") (pinfunction "PD3(INT1)_1") (pintype "bidirectional"))
      (node (ref "JP5") (pin "4") (pinfunction "4_4") (pintype "passive"))
    )
    (net (code "23") (name "IO4") (class "Default")
      (node (ref "IC2") (pin "2") (pinfunction "PD4(XCK/T0)_2") (pintype "bidirectional"))
      (node (ref "JP5") (pin "5") (pinfunction "5_5") (pintype "passive"))
    )
    (net (code "24") (name "IO5") (class "Default")
      (node (ref "IC2") (pin "9") (pinfunction "PD5(T1)_9") (pintype "bidirectional"))
      (node (ref "JP5") (pin "6") (pinfunction "6_6") (pintype "passive"))
    )
    (net (code "25") (name "IO6") (class "Default")
      (node (ref "IC2") (pin "10") (pinfunction "PD6(AIN0)_10") (pintype "bidirectional"))
      (node (ref "JP5") (pin "7") (pinfunction "7_7") (pintype "passive"))
    )
    (net (code "26") (name "IO9") (class "Default")
      (node (ref "IC2") (pin "13") (pinfunction "PB1(OC1A)_13") (pintype "bidirectional"))
      (node (ref "JP3") (pin "2") (pinfunction "2_2") (pintype "passive"))
    )
    (net (code "27") (name "M8RXD") (class "Default")
      (node (ref "IC3") (pin "1") (pinfunction "TXD_1") (pintype "output"))
      (node (ref "R4") (pin "2") (pinfunction "2_2") (pintype "passive"))
    )
    (net (code "28") (name "M8TXD") (class "Default")
      (node (ref "IC3") (pin "5") (pinfunction "RXD_5") (pintype "input"))
      (node (ref "R5") (pin "2") (pinfunction "2_2") (pintype "passive"))
    )
    (net (code "29") (name "MISO") (class "Default")
      (node (ref "IC2") (pin "16") (pinfunction "PB4(MISO)_16") (pintype "bidirectional"))
      (node (ref "JP2") (pin "1") (pinfunction "1_1") (pintype "passive"))
      (node (ref "JP3") (pin "5") (pinfunction "5_5") (pintype "passive"))
    )
    (net (code "30") (name "MOSI") (class "Default")
      (node (ref "IC2") (pin "15") (pinfunction "PB3(MOSI/OC2)_15") (pintype "bidirectional"))
      (node (ref "JP2") (pin "4") (pinfunction "4_4") (pintype "passive"))
      (node (ref "JP3") (pin "4") (pinfunction "4_4") (pintype "passive"))
      (node (ref "SJ3") (pin "1") (pinfunction "1_1") (pintype "passive"))
    )
    (net (code "31") (name "NETLIGHT") (class "Default")
      (node (ref "R22") (pin "1") (pinfunction "1_1") (pintype "passive"))
      (node (ref "U3") (pin "52") (pinfunction "NETLIGHT_52") (pintype "power_in"))
    )
    (net (code "32") (name "Net-(C23-Pad1)") (class "Default")
      (node (ref "C23") (pin "1") (pinfunction "1_1") (pintype "passive"))
      (node (ref "GPS_ANT") (pin "D") (pinfunction "D_D") (pintype "bidirectional"))
    )
    (net (code "33") (name "Net-(D5-Pad-)") (class "Default")
      (node (ref "D5") (pin "-") (pinfunction "-_-") (pintype "passive"))
      (node (ref "R26") (pin "1") (pinfunction "1_1") (pintype "passive"))
    )
    (net (code "34") (name "Net-(D6-Pad-)") (class "Default")
      (node (ref "D6") (pin "-") (pinfunction "-_-") (pintype "passive"))
      (node (ref "R25") (pin "1") (pinfunction "1_1") (pintype "passive"))
    )
    (net (code "35") (name "Net-(IC2-PB6(XTAL1{slash}TOSC1))") (class "Default")
      (node (ref "C4") (pin "2") (pinfunction "2_2") (pintype "passive"))
      (node (ref "IC2") (pin "7") (pinfunction "PB6(XTAL1/TOSC1)_7") (pintype "bidirectional"))
      (node (ref "Q6") (pin "1") (pinfunction "1_1") (pintype "passive"))
      (node (ref "R2") (pin "1") (pinfunction "1_1") (pintype "passive"))
    )
    (net (code "36") (name "Net-(IC2-PB7(XTAL2{slash}TOSC2))") (class "Default")
      (node (ref "C3") (pin "2") (pinfunction "2_2") (pintype "passive"))
      (node (ref "IC2") (pin "8") (pinfunction "PB7(XTAL2/TOSC2)_8") (pintype "bidirectional"))
      (node (ref "Q6") (pin "3") (pinfunction "2_3") (pintype "passive"))
      (node (ref "R2") (pin "2") (pinfunction "2_2") (pintype "passive"))
    )
    (net (code "37") (name "Net-(IC3-3V3OUT)") (class "Default")
      (node (ref "C9") (pin "1") (pinfunction "1_1") (pintype "passive"))
      (node (ref "IC3") (pin "17") (pinfunction "3V3OUT_17") (pintype "output"))
    )
    (net (code "38") (name "Net-(L4-Pad2)") (class "Default")
      (node (ref "L4") (pin "2") (pinfunction "2_2") (pintype "passive"))
      (node (ref "X2") (pin "VBUS") (pinfunction "VBUS_VBUS") (pintype "power_in"))
    )
    (net (code "39") (name "Net-(L5-Pad2)") (class "Default")
      (node (ref "L5") (pin "2") (pinfunction "2_2") (pintype "passive"))
      (node (ref "X2") (pin "BASE@1") (pinfunction "P$1_BASE@1") (pintype "bidirectional"))
      (node (ref "X2") (pin "BASE@2") (pinfunction "P$1_BASE@2") (pintype "bidirectional"))
      (node (ref "X2") (pin "SPRT@1") (pinfunction "P$1_SPRT@1") (pintype "bidirectional"))
      (node (ref "X2") (pin "SPRT@2") (pinfunction "P$1_SPRT@2") (pintype "bidirectional"))
      (node (ref "X2") (pin "SPRT@3") (pinfunction "P$1_SPRT@3") (pintype "bidirectional"))
      (node (ref "X2") (pin "SPRT@4") (pinfunction "P$1_SPRT@4") (pintype "bidirectional"))
    )
    (net (code "40") (name "Net-(LED1-PadA)") (class "Default")
      (node (ref "LED1") (pin "A") (pinfunction "A_A") (pintype "passive"))
      (node (ref "R6") (pin "1") (pinfunction "1_1") (pintype "passive"))
    )
    (net (code "41") (name "Net-(LED2-PadA)") (class "Default")
      (node (ref "LED2") (pin "A") (pinfunction "A_A") (pintype "passive"))
      (node (ref "R7") (pin "1") (pinfunction "1_1") (pintype "passive"))
    )
    (net (code "42") (name "Net-(Q2-B)") (class "Default")
      (node (ref "Q2") (pin "1") (pinfunction "B_1") (pintype "passive"))
      (node (ref "R19") (pin "2") (pinfunction "2_2") (pintype "passive"))
      (node (ref "R20") (pin "1") (pinfunction "1_1") (pintype "passive"))
    )
    (net (code "43") (name "Net-(Q3-B)") (class "Default")
      (node (ref "Q3") (pin "1") (pinfunction "B_1") (pintype "passive"))
      (node (ref "R21") (pin "2") (pinfunction "2_2") (pintype "passive"))
      (node (ref "R23") (pin "1") (pinfunction "1_1") (pintype "passive"))
    )
    (net (code "44") (name "Net-(Q3-C)") (class "Default")
      (node (ref "Q3") (pin "3") (pinfunction "C_3") (pintype "passive"))
      (node (ref "R25") (pin "2") (pinfunction "2_2") (pintype "passive"))
    )
    (net (code "45") (name "Net-(Q4-B)") (class "Default")
      (node (ref "Q4") (pin "1") (pinfunction "B_1") (pintype "passive"))
      (node (ref "R22") (pin "2") (pinfunction "2_2") (pintype "passive"))
      (node (ref "R24") (pin "1") (pinfunction "1_1") (pintype "passive"))
    )
    (net (code "46") (name "Net-(Q4-C)") (class "Default")
      (node (ref "Q4") (pin "3") (pinfunction "C_3") (pintype "passive"))
      (node (ref "R26") (pin "2") (pinfunction "2_2") (pintype "passive"))
    )
    (net (code "47") (name "Net-(Q5-B)") (class "Default")
      (node (ref "Q5") (pin "1") (pinfunction "B_1") (pintype "passive"))
      (node (ref "R27") (pin "2") (pinfunction "2_2") (pintype "passive"))
      (node (ref "R28") (pin "1") (pinfunction "1_1") (pintype "passive"))
    )
    (net (code "48") (name "Net-(R8-Pad1)") (class "Default")
      (node (ref "R8") (pin "1") (pinfunction "1_1") (pintype "passive"))
      (node (ref "TX") (pin "A") (pinfunction "A_A") (pintype "passive"))
    )
    (net (code "49") (name "Net-(R9-Pad1)") (class "Default")
      (node (ref "R9") (pin "1") (pinfunction "1_1") (pintype "passive"))
      (node (ref "RX") (pin "A") (pinfunction "A_A") (pintype "passive"))
    )
    (net (code "50") (name "Net-(T1-S)") (class "Default")
      (node (ref "D2") (pin "A") (pinfunction "A_A") (pintype "passive"))
      (node (ref "T1") (pin "2") (pinfunction "S_2") (pintype "passive"))
    )
    (net (code "51") (name "Net-(U1-ADJ)") (class "Default")
      (node (ref "R13") (pin "2") (pinfunction "2_2") (pintype "passive"))
      (node (ref "R14") (pin "1") (pinfunction "1_1") (pintype "passive"))
      (node (ref "U1") (pin "5") (pinfunction "ADJ_5") (pintype "bidirectional"))
    )
    (net (code "52") (name "Net-(U1-OUT)") (class "Default")
      (node (ref "C18") (pin "+") (pinfunction "+_+") (pintype "passive"))
      (node (ref "C20") (pin "2") (pinfunction "2_2") (pintype "passive"))
      (node (ref "L3") (pin "2") (pinfunction "2_2") (pintype "passive"))
      (node (ref "R14") (pin "2") (pinfunction "2_2") (pintype "passive"))
      (node (ref "R15") (pin "2") (pinfunction "2_2") (pintype "passive"))
      (node (ref "U1") (pin "4") (pinfunction "OUT_4") (pintype "bidirectional"))
    )
    (net (code "53") (name "Net-(U2-CLK)") (class "Default")
      (node (ref "R17") (pin "1") (pinfunction "1_1") (pintype "passive"))
      (node (ref "U2") (pin "3") (pinfunction "CLK_3") (pintype "bidirectional"))
    )
    (net (code "54") (name "Net-(U2-I{slash}O)") (class "Default")
      (node (ref "R18") (pin "2") (pinfunction "2_2") (pintype "passive"))
      (node (ref "U2") (pin "7") (pinfunction "I/O_7") (pintype "bidirectional"))
    )
    (net (code "55") (name "Net-(U2-RST)") (class "Default")
      (node (ref "R16") (pin "1") (pinfunction "1_1") (pintype "passive"))
      (node (ref "U2") (pin "2") (pinfunction "RST_2") (pintype "bidirectional"))
    )
    (net (code "56") (name "Net-(U4-A8)") (class "Default")
      (node (ref "R12") (pin "1") (pinfunction "1_1") (pintype "passive"))
      (node (ref "U4") (pin "9") (pinfunction "A8_9") (pintype "bidirectional"))
    )
    (net (code "57") (name "Net-(U4-B8)") (class "Default")
      (node (ref "R29") (pin "1") (pinfunction "1_1") (pintype "passive"))
      (node (ref "U4") (pin "12") (pinfunction "B8_12") (pintype "bidirectional"))
    )
    (net (code "58") (name "PWRIN") (class "Default")
      (node (ref "C10") (pin "2") (pinfunction "2_2") (pintype "power_in"))
      (node (ref "D1") (pin "A") (pinfunction "A_A") (pintype "passive"))
      (node (ref "R10") (pin "2") (pinfunction "2_2") (pintype "passive"))
    )
    (net (code "59") (name "PWRKEY") (class "Default")
      (node (ref "C30") (pin "2") (pinfunction "2_2") (pintype "passive"))
      (node (ref "PWR") (pin "2") (pinfunction "S_2") (pintype "passive"))
      (node (ref "Q2") (pin "3") (pinfunction "C_3") (pintype "passive"))
      (node (ref "U3") (pin "1") (pinfunction "PWRKEY_1") (pintype "input"))
    )
    (net (code "60") (name "RESET") (class "Default")
      (node (ref "C2") (pin "2") (pinfunction "2_2") (pintype "passive"))
      (node (ref "IC2") (pin "29") (pinfunction "PC6(/RESET)_29") (pintype "bidirectional"))
      (node (ref "JP1") (pin "1") (pinfunction "1_1") (pintype "passive"))
      (node (ref "JP2") (pin "5") (pinfunction "5_5") (pintype "passive"))
      (node (ref "R3") (pin "1") (pinfunction "1_1") (pintype "passive"))
      (node (ref "RESET") (pin "1") (pinfunction "P_1") (pintype "passive"))
      (node (ref "SJ1") (pin "1") (pinfunction "1_1") (pintype "passive"))
      (node (ref "SJ1") (pin "2") (pinfunction "2_2") (pintype "passive"))
    )
    (net (code "61") (name "RF_ANT") (class "Default")
      (node (ref "RF_ANT") (pin "D") (pinfunction "D_D") (pintype "bidirectional"))
      (node (ref "U3") (pin "60") (pinfunction "RF_ANT_60") (pintype "power_in"))
    )
    (net (code "62") (name "RXLED") (class "Default")
      (node (ref "IC3") (pin "22") (pinfunction "RXLED_22") (pintype "input"))
      (node (ref "RX") (pin "C") (pinfunction "C_C") (pintype "passive"))
    )
    (net (code "63") (name "SCK") (class "Default")
      (node (ref "IC2") (pin "17") (pinfunction "PB5(SCK)_17") (pintype "bidirectional"))
      (node (ref "JP2") (pin "3") (pinfunction "3_3") (pintype "passive"))
      (node (ref "JP3") (pin "6") (pinfunction "6_6") (pintype "passive"))
      (node (ref "R7") (pin "2") (pinfunction "2_2") (pintype "passive"))
      (node (ref "SJ2") (pin "1") (pinfunction "1_1") (pintype "passive"))
    )
    (net (code "64") (name "SIM7000_PWRKEY_MCU") (class "Default")
      (node (ref "R19") (pin "1") (pinfunction "1_1") (pintype "passive"))
      (node (ref "SJ2") (pin "2") (pinfunction "2_2") (pintype "passive"))
    )
    (net (code "65") (name "SIM7000_RESET") (class "Default")
      (node (ref "C29") (pin "2") (pinfunction "2_2") (pintype "passive"))
      (node (ref "Q5") (pin "3") (pinfunction "C_3") (pintype "passive"))
      (node (ref "RST") (pin "2") (pinfunction "S_2") (pintype "passive"))
      (node (ref "U3") (pin "16") (pinfunction "NRESET_16") (pintype "input"))
    )
    (net (code "66") (name "SIM7000_RESET_MCU") (class "Default")
      (node (ref "R27") (pin "1") (pinfunction "1_1") (pintype "passive"))
      (node (ref "SJ3") (pin "2") (pinfunction "2_2") (pintype "passive"))
    )
    (net (code "67") (name "SIM7000_RXD") (class "Default")
      (node (ref "U3") (pin "10") (pinfunction "RXD_10") (pintype "input"))
      (node (ref "U4") (pin "3") (pinfunction "A2_3") (pintype "bidirectional"))
    )
    (net (code "68") (name "SIM7000_TXD") (class "Default")
      (node (ref "U3") (pin "9") (pinfunction "TXD_9") (pintype "output"))
      (node (ref "U4") (pin "1") (pinfunction "A1_1") (pintype "bidirectional"))
    )
    (net (code "69") (name "SIM_ADC") (class "Default")
      (node (ref "U3") (pin "25") (pinfunction "ADC_25") (pintype "input"))
    )
    (net (code "70") (name "SIM_CLK") (class "Default")
      (node (ref "C24") (pin "2") (pinfunction "2_2") (pintype "passive"))
      (node (ref "D4") (pin "5") (pinfunction "C4_5") (pintype "passive"))
      (node (ref "R17") (pin "2") (pinfunction "2_2") (pintype "passive"))
      (node (ref "U3") (pin "32") (pinfunction "SIM_CLK_32") (pintype "output"))
    )
    (net (code "71") (name "SIM_DATA") (class "Default")
      (node (ref "C26") (pin "2") (pinfunction "2_2") (pintype "passive"))
      (node (ref "D4") (pin "4") (pinfunction "C3_4") (pintype "passive"))
      (node (ref "R18") (pin "1") (pinfunction "1_1") (pintype "passive"))
      (node (ref "U3") (pin "31") (pinfunction "SIM_DATA_31") (pintype "output"))
    )
    (net (code "72") (name "SIM_GPIO0") (class "Default")
      (node (ref "U3") (pin "50") (pinfunction "GPIO0_50") (pintype "bidirectional"))
    )
    (net (code "73") (name "SIM_GPIO1") (class "Default")
      (node (ref "U3") (pin "49") (pinfunction "GPIO1_49") (pintype "bidirectional"))
    )
    (net (code "74") (name "SIM_GPIO2") (class "Default")
      (node (ref "U3") (pin "67") (pinfunction "GPIO2_67") (pintype "power_in"))
    )
    (net (code "75") (name "SIM_GPIO3") (class "Default")
      (node (ref "U3") (pin "68") (pinfunction "GPIO3_68") (pintype "power_in"))
    )
    (net (code "76") (name "SIM_GPIO4") (class "Default")
      (node (ref "U3") (pin "48") (pinfunction "GPIO4_48") (pintype "input"))
    )
    (net (code "77") (name "SIM_I2C_SCL") (class "Default")
      (node (ref "U3") (pin "38") (pinfunction "SCL_38") (pintype "output"))
    )
    (net (code "78") (name "SIM_I2C_SDA") (class "Default")
      (node (ref "U3") (pin "37") (pinfunction "SDA_37") (pintype "bidirectional"))
    )
    (net (code "79") (name "SIM_RST") (class "Default")
      (node (ref "C25") (pin "2") (pinfunction "2_2") (pintype "passive"))
      (node (ref "D4") (pin "3") (pinfunction "C2_3") (pintype "passive"))
      (node (ref "R16") (pin "2") (pinfunction "2_2") (pintype "passive"))
      (node (ref "U3") (pin "33") (pinfunction "SIM_RST_33") (pintype "bidirectional"))
    )
    (net (code "80") (name "SIM_USB_DM") (class "Default")
      (node (ref "U3") (pin "28") (pinfunction "USB_DM_28") (pintype "output"))
      (node (ref "X2") (pin "D-") (pinfunction "D-_D-") (pintype "bidirectional"))
    )
    (net (code "81") (name "SIM_USB_DP") (class "Default")
      (node (ref "U3") (pin "27") (pinfunction "USB_DP_27") (pintype "bidirectional"))
      (node (ref "X2") (pin "D+") (pinfunction "D+_D+") (pintype "bidirectional"))
    )
    (net (code "82") (name "SIM_VDD") (class "Default")
      (node (ref "C22") (pin "1") (pinfunction "1_1") (pintype "passive"))
      (node (ref "D4") (pin "1") (pinfunction "C1_1") (pintype "passive"))
      (node (ref "U2") (pin "1") (pinfunction "VCC_1") (pintype "bidirectional"))
      (node (ref "U3") (pin "30") (pinfunction "SIM_VDD_30") (pintype "input"))
    )
    (net (code "83") (name "SS") (class "Default")
      (node (ref "IC2") (pin "14") (pinfunction "PB2(SS/OC1B)_14") (pintype "bidirectional"))
      (node (ref "JP3") (pin "3") (pinfunction "3_3") (pintype "passive"))
    )
    (net (code "84") (name "STATUS") (class "Default")
      (node (ref "R21") (pin "1") (pinfunction "1_1") (pintype "passive"))
      (node (ref "U3") (pin "66") (pinfunction "STATUS_66") (pintype "power_in"))
    )
    (net (code "85") (name "TXLED") (class "Default")
      (node (ref "IC3") (pin "23") (pinfunction "TXLED_23") (pintype "input"))
      (node (ref "TX") (pin "C") (pinfunction "C_C") (pintype "passive"))
    )
    (net (code "86") (name "USHIELD") (class "Default")
      (node (ref "C31") (pin "2") (pinfunction "2_2") (pintype "passive"))
      (node (ref "L1") (pin "2") (pinfunction "2_2") (pintype "passive"))
      (node (ref "R30") (pin "1") (pinfunction "1_1") (pintype "passive"))
      (node (ref "X1") (pin "P$1") (pinfunction "P$1_P$1") (pintype "bidirectional"))
      (node (ref "X1") (pin "P$2") (pinfunction "P$2_P$2") (pintype "bidirectional"))
    )
    (net (code "87") (name "V+") (class "Default")
      (node (ref "C34") (pin "1") (pinfunction "1_1") (pintype "passive"))
      (node (ref "C35") (pin "1") (pinfunction "1_1") (pintype "passive"))
      (node (ref "C36") (pin "1") (pinfunction "1_1") (pintype "passive"))
      (node (ref "D5") (pin "+") (pinfunction "+_+") (pintype "passive"))
      (node (ref "D6") (pin "+") (pinfunction "+_+") (pintype "passive"))
      (node (ref "L3") (pin "1") (pinfunction "1_1") (pintype "passive"))
      (node (ref "U3") (pin "55") (pinfunction "VBAT_55") (pintype "power_in"))
      (node (ref "U3") (pin "56") (pinfunction "VBAT_56") (pintype "power_in"))
      (node (ref "U3") (pin "57") (pinfunction "VBAT_57") (pintype "power_in"))
    )
    (net (code "88") (name "VDD_EXT") (class "Default")
      (node (ref "C27") (pin "2") (pinfunction "2_2") (pintype "passive"))
      (node (ref "U3") (pin "15") (pinfunction "VDD_EXT_15") (pintype "output"))
      (node (ref "U4") (pin "10") (pinfunction "OE_10") (pintype "bidirectional"))
      (node (ref "U4") (pin "2") (pinfunction "VCCA_2") (pintype "bidirectional"))
    )
    (net (code "89") (name "VIN") (class "Default")
      (node (ref "C11") (pin "1") (pinfunction "1_1") (pintype "passive"))
      (node (ref "C13") (pin "2") (pinfunction "2_2") (pintype "passive"))
      (node (ref "C14") (pin "2") (pinfunction "2_2") (pintype "passive"))
      (node (ref "C16") (pin "+") (pinfunction "+_+") (pintype "passive"))
      (node (ref "D1") (pin "C") (pinfunction "C_C") (pintype "passive"))
      (node (ref "D2") (pin "C") (pinfunction "C_C") (pintype "passive"))
      (node (ref "IC4") (pin "3") (pinfunction "IN_3") (pintype "input"))
      (node (ref "JP1") (pin "6") (pinfunction "6_6") (pintype "passive"))
      (node (ref "U1") (pin "1") (pinfunction "EN_1") (pintype "bidirectional"))
      (node (ref "U1") (pin "2") (pinfunction "IN_2") (pintype "bidirectional"))
    )
    (net (code "90") (name "XUSB") (class "Default")
      (node (ref "L2") (pin "2") (pinfunction "2_2") (pintype "passive"))
      (node (ref "X1") (pin "1") (pinfunction "1_1") (pintype "bidirectional"))
    )
    (net (code "91") (name "unconnected-(D4-C5-Pad6)") (class "Default")
      (node (ref "D4") (pin "6") (pinfunction "C5_6") (pintype "passive"))
    )
    (net (code "92") (name "unconnected-(IC1B-OUT-Pad7)") (class "Default")
      (node (ref "IC1") (pin "7") (pinfunction "OUT_7") (pintype "output"))
    )
    (net (code "93") (name "unconnected-(IC2-ADC6-Pad19)") (class "Default")
      (node (ref "IC2") (pin "19") (pinfunction "ADC6_19") (pintype "bidirectional"))
    )
    (net (code "94") (name "unconnected-(IC2-ADC7-Pad22)") (class "Default")
      (node (ref "IC2") (pin "22") (pinfunction "ADC7_22") (pintype "bidirectional"))
    )
    (net (code "95") (name "unconnected-(IC3-CTS-Pad11)") (class "Default")
      (node (ref "IC3") (pin "11") (pinfunction "CTS_11") (pintype "input"))
    )
    (net (code "96") (name "unconnected-(IC3-DCD-Pad10)") (class "Default")
      (node (ref "IC3") (pin "10") (pinfunction "DCD_10") (pintype "input"))
    )
    (net (code "97") (name "unconnected-(IC3-DSR-Pad9)") (class "Default")
      (node (ref "IC3") (pin "9") (pinfunction "DSR_9") (pintype "input"))
    )
    (net (code "98") (name "unconnected-(IC3-OSCI-Pad27)") (class "Default")
      (node (ref "IC3") (pin "27") (pinfunction "OSCI_27") (pintype "input"))
    )
    (net (code "99") (name "unconnected-(IC3-OSCO-Pad28)") (class "Default")
      (node (ref "IC3") (pin "28") (pinfunction "OSCO_28") (pintype "output"))
    )
    (net (code "100") (name "unconnected-(IC3-PWREN-Pad14)") (class "Default")
      (node (ref "IC3") (pin "14") (pinfunction "PWREN_14") (pintype "input"))
    )
    (net (code "101") (name "unconnected-(IC3-RESET-Pad19)") (class "Default")
      (node (ref "IC3") (pin "19") (pinfunction "RESET_19") (pintype "input"))
    )
    (net (code "102") (name "unconnected-(IC3-RI-Pad6)") (class "Default")
      (node (ref "IC3") (pin "6") (pinfunction "RI_6") (pintype "input"))
    )
    (net (code "103") (name "unconnected-(IC3-RTS-Pad3)") (class "Default")
      (node (ref "IC3") (pin "3") (pinfunction "RTS_3") (pintype "output"))
    )
    (net (code "104") (name "unconnected-(IC3-SLEEP-Pad12)") (class "Default")
      (node (ref "IC3") (pin "12") (pinfunction "SLEEP_12") (pintype "input"))
    )
    (net (code "105") (name "unconnected-(IC3-TXDEN-Pad13)") (class "Default")
      (node (ref "IC3") (pin "13") (pinfunction "TXDEN_13") (pintype "input"))
    )
    (net (code "106") (name "unconnected-(U2-VPP-Pad6)") (class "Default")
      (node (ref "U2") (pin "6") (pinfunction "VPP_6") (pintype "bidirectional"))
    )
    (net (code "107") (name "unconnected-(U3-BOOT_CFG-Pad6)") (class "Default")
      (node (ref "U3") (pin "6") (pinfunction "BOOT_CFG_6") (pintype "output"))
    )
    (net (code "108") (name "unconnected-(U3-CTS-Pad7)") (class "Default")
      (node (ref "U3") (pin "7") (pinfunction "CTS_7") (pintype "output"))
    )
    (net (code "109") (name "unconnected-(U3-DCD-Pad5)") (class "Default")
      (node (ref "U3") (pin "5") (pinfunction "DCD_5") (pintype "output"))
    )
    (net (code "110") (name "unconnected-(U3-DTR-Pad3)") (class "Default")
      (node (ref "U3") (pin "3") (pinfunction "DTR_3") (pintype "input"))
    )
    (net (code "111") (name "unconnected-(U3-MDM_LOG_TX-Pad23)") (class "Default")
      (node (ref "U3") (pin "23") (pinfunction "MDM_LOG_TX_23") (pintype "input"))
    )
    (net (code "112") (name "unconnected-(U3-NC-Pad19)") (class "Default")
      (node (ref "U3") (pin "19") (pinfunction "NC_19") (pintype "input"))
    )
    (net (code "113") (name "unconnected-(U3-NC-Pad20)") (class "Default")
      (node (ref "U3") (pin "20") (pinfunction "NC_20") (pintype "output"))
    )
    (net (code "114") (name "unconnected-(U3-NC-Pad21)") (class "Default")
      (node (ref "U3") (pin "21") (pinfunction "NC_21") (pintype "output"))
    )
    (net (code "115") (name "unconnected-(U3-NC-Pad22)") (class "Default")
      (node (ref "U3") (pin "22") (pinfunction "NC_22") (pintype "input"))
    )
    (net (code "116") (name "unconnected-(U3-NC-Pad26)") (class "Default")
      (node (ref "U3") (pin "26") (pinfunction "NC_26") (pintype "output"))
    )
    (net (code "117") (name "unconnected-(U3-NC-Pad35)") (class "Default")
      (node (ref "U3") (pin "35") (pinfunction "NC_35") (pintype "input"))
    )
    (net (code "118") (name "unconnected-(U3-NC-Pad36)") (class "Default")
      (node (ref "U3") (pin "36") (pinfunction "NC_36") (pintype "output"))
    )
    (net (code "119") (name "unconnected-(U3-NC-Pad40)") (class "Default")
      (node (ref "U3") (pin "40") (pinfunction "NC_40") (pintype "output"))
    )
    (net (code "120") (name "unconnected-(U3-NC-Pad41)") (class "Default")
      (node (ref "U3") (pin "41") (pinfunction "NC_41") (pintype "output"))
    )
    (net (code "121") (name "unconnected-(U3-NC-Pad42)") (class "Default")
      (node (ref "U3") (pin "42") (pinfunction "NC_42") (pintype "output"))
    )
    (net (code "122") (name "unconnected-(U3-NC-Pad43)") (class "Default")
      (node (ref "U3") (pin "43") (pinfunction "NC_43") (pintype "output"))
    )
    (net (code "123") (name "unconnected-(U3-NC-Pad44)") (class "Default")
      (node (ref "U3") (pin "44") (pinfunction "NC_44") (pintype "output"))
    )
    (net (code "124") (name "unconnected-(U3-NC-Pad47)") (class "Default")
      (node (ref "U3") (pin "47") (pinfunction "NC_47") (pintype "input"))
    )
    (net (code "125") (name "unconnected-(U3-NC-Pad51)") (class "Default")
      (node (ref "U3") (pin "51") (pinfunction "NC_51") (pintype "bidirectional"))
    )
    (net (code "126") (name "unconnected-(U3-PCM_CLK-Pad11)") (class "Default")
      (node (ref "U3") (pin "11") (pinfunction "PCM_CLK_11") (pintype "output"))
    )
    (net (code "127") (name "unconnected-(U3-PCM_DIN-Pad13)") (class "Default")
      (node (ref "U3") (pin "13") (pinfunction "PCM_DIN_13") (pintype "output"))
    )
    (net (code "128") (name "unconnected-(U3-PCM_DOUT-Pad14)") (class "Default")
      (node (ref "U3") (pin "14") (pinfunction "PCM_DOUT_14") (pintype "output"))
    )
    (net (code "129") (name "unconnected-(U3-PCM_SYNC-Pad12)") (class "Default")
      (node (ref "U3") (pin "12") (pinfunction "PCM_SYNC_12") (pintype "bidirectional"))
    )
    (net (code "130") (name "unconnected-(U3-RI-Pad4)") (class "Default")
      (node (ref "U3") (pin "4") (pinfunction "RI_4") (pintype "output"))
    )
    (net (code "131") (name "unconnected-(U3-RTS-Pad8)") (class "Default")
      (node (ref "U3") (pin "8") (pinfunction "RTS_8") (pintype "input"))
    )
    (net (code "132") (name "unconnected-(U3-SIM_DET-Pad34)") (class "Default")
      (node (ref "U3") (pin "34") (pinfunction "SIM_DET_34") (pintype "bidirectional"))
    )
    (net (code "133") (name "unconnected-(U4-A3-Pad4)") (class "Default")
      (node (ref "U4") (pin "4") (pinfunction "A3_4") (pintype "bidirectional"))
    )
    (net (code "134") (name "unconnected-(U4-A4-Pad5)") (class "Default")
      (node (ref "U4") (pin "5") (pinfunction "A4_5") (pintype "bidirectional"))
    )
    (net (code "135") (name "unconnected-(U4-A5-Pad6)") (class "Default")
      (node (ref "U4") (pin "6") (pinfunction "A5_6") (pintype "bidirectional"))
    )
    (net (code "136") (name "unconnected-(U4-A6-Pad7)") (class "Default")
      (node (ref "U4") (pin "7") (pinfunction "A6_7") (pintype "bidirectional"))
    )
    (net (code "137") (name "unconnected-(U4-A7-Pad8)") (class "Default")
      (node (ref "U4") (pin "8") (pinfunction "A7_8") (pintype "bidirectional"))
    )
    (net (code "138") (name "unconnected-(U4-B3-Pad17)") (class "Default")
      (node (ref "U4") (pin "17") (pinfunction "B3_17") (pintype "bidirectional"))
    )
    (net (code "139") (name "unconnected-(U4-B4-Pad16)") (class "Default")
      (node (ref "U4") (pin "16") (pinfunction "B4_16") (pintype "bidirectional"))
    )
    (net (code "140") (name "unconnected-(U4-B5-Pad15)") (class "Default")
      (node (ref "U4") (pin "15") (pinfunction "B5_15") (pintype "bidirectional"))
    )
    (net (code "141") (name "unconnected-(U4-B6-Pad14)") (class "Default")
      (node (ref "U4") (pin "14") (pinfunction "B6_14") (pintype "bidirectional"))
    )
    (net (code "142") (name "unconnected-(U4-B7-Pad13)") (class "Default")
      (node (ref "U4") (pin "13") (pinfunction "B7_13") (pintype "bidirectional"))
    )
    (net (code "143") (name "unconnected-(X2-PadID)") (class "Default")
      (node (ref "X2") (pin "ID") (pinfunction "ID_ID") (pintype "bidirectional"))
    )
  )
)
